# pyra_dvt1_power-2_0.net
KiCad netlist of a schematic drawn in Altium Designer
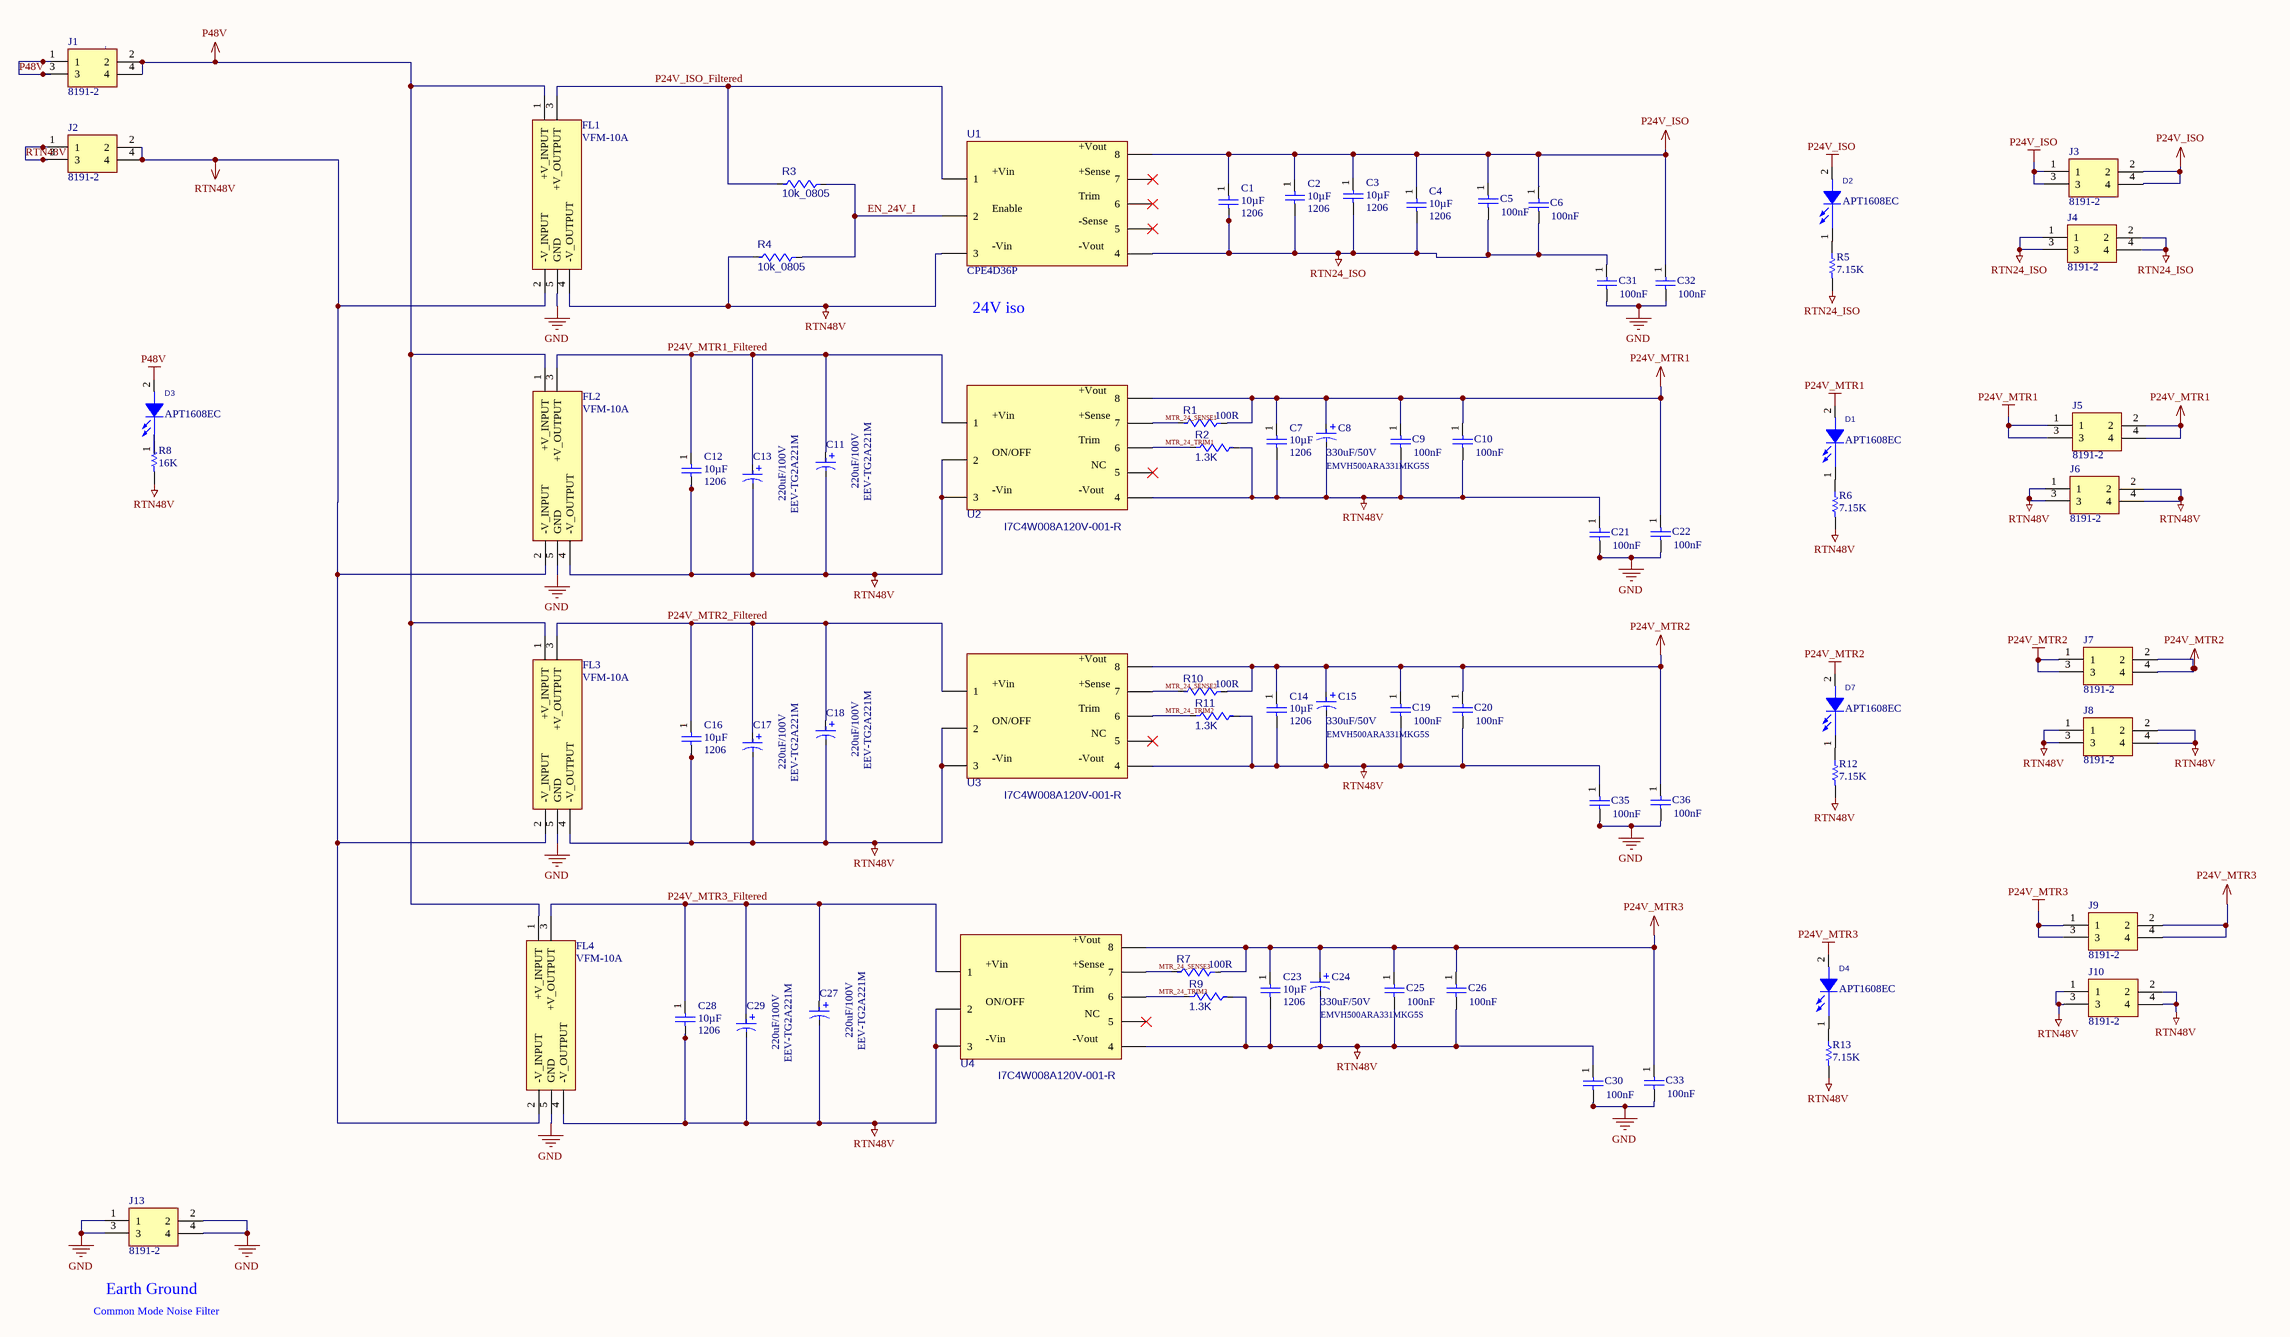
[diagram p0: pyra_dvt1_power-2.0.SchDoc]

(export (version "E")
  (design (tool "Eeschema 10.0.6"))
  (components
    (comp (ref "C1")
      (value "10µF")
      (footprint "1206")
      (description "CAP CER 10UF 50V X5R 1206")
      (fields
        (field (name "MANUFACTURER") "TDK Corporation")
        (field (name "TOLERANCE") "±20%")
        (field (name "SIZE") "1206")
      )
      (libsource (lib "bct") (part "C1206_10UF_50V"))
    )
    (comp (ref "C2")
      (value "10µF")
      (footprint "1206")
      (description "CAP CER 10UF 50V X5R 1206")
      (fields
        (field (name "MANUFACTURER") "TDK Corporation")
        (field (name "TOLERANCE") "±20%")
        (field (name "SIZE") "1206")
      )
      (libsource (lib "bct") (part "C1206_10UF_50V"))
    )
    (comp (ref "C3")
      (value "10µF")
      (footprint "1206")
      (description "CAP CER 10UF 50V X5R 1206")
      (fields
        (field (name "MANUFACTURER") "TDK Corporation")
        (field (name "TOLERANCE") "±20%")
        (field (name "SIZE") "1206")
      )
      (libsource (lib "bct") (part "C1206_10UF_50V"))
    )
    (comp (ref "C4")
      (value "10µF")
      (footprint "1206")
      (description "CAP CER 10UF 50V X5R 1206")
      (fields
        (field (name "MANUFACTURER") "TDK Corporation")
        (field (name "TOLERANCE") "±20%")
        (field (name "SIZE") "1206")
      )
      (libsource (lib "bct") (part "C1206_10UF_50V"))
    )
    (comp (ref "C5")
      (value "100nF")
      (footprint "0603R(1608)")
      (description "CAP CER 0.1UF 50V X5R 0603")
      (fields (field (name "MANUFACTURER") "TDK Corporation") (field (name "TOLERANCE") "±10%"))
      (libsource (lib "bct") (part "C0603_100NF_50V"))
    )
    (comp (ref "C6")
      (value "100nF")
      (footprint "0603R(1608)")
      (description "CAP CER 0.1UF 50V X5R 0603")
      (fields (field (name "MANUFACTURER") "TDK Corporation") (field (name "TOLERANCE") "±10%"))
      (libsource (lib "bct") (part "C0603_100NF_50V"))
    )
    (comp (ref "C7")
      (value "10µF")
      (footprint "1206")
      (description "CAP CER 10UF 50V X5R 1206")
      (fields
        (field (name "MANUFACTURER") "TDK Corporation")
        (field (name "TOLERANCE") "±20%")
        (field (name "SIZE") "1206")
      )
      (libsource (lib "bct") (part "C1206_10UF_50V"))
    )
    (comp (ref "C8")
      (value "330uF/50V")
      (footprint "EMVH500ARA331MKG5S")
      (description "CAP ALUM 330UF 20% 50V SMD")
      (fields
        (field (name "MANUFACTURER") "United Chemi-con")
        (field (name "MANUFACTURER PART NUMBER") "EMVH500ARA331MKG5S")
        (field (name "TOLERANCE") "20%")
        (field (name "_VERIFIED FOOTPRINT") ".mfr-pn? footprint?")
        (field (name "_VERIFIED SYMBOL") ".mfr-pn?")
        (field (name "_VERIFIED BOM") ".mfr-pn?")
      )
      (libsource (lib "PowerPCB") (part "CAP POLAR  330uF"))
    )
    (comp (ref "C9")
      (value "100nF")
      (footprint "0603R(1608)")
      (description "CAP CER 0.1UF 50V X5R 0603")
      (fields (field (name "MANUFACTURER") "TDK Corporation") (field (name "TOLERANCE") "±10%"))
      (libsource (lib "bct") (part "C0603_100NF_50V"))
    )
    (comp (ref "C10")
      (value "100nF")
      (footprint "0603R(1608)")
      (description "CAP CER 0.1UF 50V X5R 0603")
      (fields (field (name "MANUFACTURER") "TDK Corporation") (field (name "TOLERANCE") "±10%"))
      (libsource (lib "bct") (part "C0603_100NF_50V"))
    )
    (comp (ref "C11")
      (value "220uF/100V")
      (footprint "EMVH101GDA221MMN0S")
      (description "CAP ALUM 220UF 20% 100V SMD")
      (fields
        (field (name "MANUFACTURER") "Panasonic")
        (field (name "MANUFACTURER PART NUMBER") "EEV-TG2A221M")
        (field (name "TOLERANCE") "20%")
        (field (name "_VERIFIED FOOTPRINT") ".mfr-pn? footprint?")
        (field (name "_VERIFIED SYMBOL") ".mfr-pn?")
        (field (name "_VERIFIED BOM") ".mfr-pn?")
      )
      (libsource (lib "PowerPCB") (part "CAP POLAR  220uF"))
    )
    (comp (ref "C12")
      (value "10µF")
      (footprint "1206")
      (description "CAP CER 10UF 50V X5R 1206")
      (fields
        (field (name "MANUFACTURER") "TDK Corporation")
        (field (name "TOLERANCE") "±20%")
        (field (name "SIZE") "1206")
      )
      (libsource (lib "bct") (part "C1206_10UF_50V"))
    )
    (comp (ref "C13")
      (value "220uF/100V")
      (footprint "EMVH101GDA221MMN0S")
      (description "CAP ALUM 220UF 20% 100V SMD")
      (fields
        (field (name "MANUFACTURER") "Panasonic")
        (field (name "MANUFACTURER PART NUMBER") "EEV-TG2A221M")
        (field (name "TOLERANCE") "20%")
        (field (name "_VERIFIED FOOTPRINT") ".mfr-pn? footprint?")
        (field (name "_VERIFIED SYMBOL") ".mfr-pn?")
        (field (name "_VERIFIED BOM") ".mfr-pn?")
      )
      (libsource (lib "PowerPCB") (part "CAP POLAR  220uF"))
    )
    (comp (ref "C14")
      (value "10µF")
      (footprint "1206")
      (description "CAP CER 10UF 50V X5R 1206")
      (fields
        (field (name "MANUFACTURER") "TDK Corporation")
        (field (name "TOLERANCE") "±20%")
        (field (name "SIZE") "1206")
      )
      (libsource (lib "bct") (part "C1206_10UF_50V"))
    )
    (comp (ref "C15")
      (value "330uF/50V")
      (footprint "EMVH500ARA331MKG5S")
      (description "CAP ALUM 330UF 20% 50V SMD")
      (fields
        (field (name "MANUFACTURER") "United Chemi-con")
        (field (name "MANUFACTURER PART NUMBER") "EMVH500ARA331MKG5S")
        (field (name "TOLERANCE") "20%")
        (field (name "_VERIFIED FOOTPRINT") ".mfr-pn? footprint?")
        (field (name "_VERIFIED SYMBOL") ".mfr-pn?")
        (field (name "_VERIFIED BOM") ".mfr-pn?")
      )
      (libsource (lib "PowerPCB") (part "CAP POLAR  330uF"))
    )
    (comp (ref "C16")
      (value "10µF")
      (footprint "1206")
      (description "CAP CER 10UF 50V X5R 1206")
      (fields
        (field (name "MANUFACTURER") "TDK Corporation")
        (field (name "TOLERANCE") "±20%")
        (field (name "SIZE") "1206")
      )
      (libsource (lib "bct") (part "C1206_10UF_50V"))
    )
    (comp (ref "C17")
      (value "220uF/100V")
      (footprint "EMVH101GDA221MMN0S")
      (description "CAP ALUM 220UF 20% 100V SMD")
      (fields
        (field (name "MANUFACTURER") "Panasonic")
        (field (name "MANUFACTURER PART NUMBER") "EEV-TG2A221M")
        (field (name "TOLERANCE") "20%")
        (field (name "_VERIFIED FOOTPRINT") ".mfr-pn? footprint?")
        (field (name "_VERIFIED SYMBOL") ".mfr-pn?")
        (field (name "_VERIFIED BOM") ".mfr-pn?")
      )
      (libsource (lib "PowerPCB") (part "CAP POLAR  220uF"))
    )
    (comp (ref "C18")
      (value "220uF/100V")
      (footprint "EMVH101GDA221MMN0S")
      (description "CAP ALUM 220UF 20% 100V SMD")
      (fields
        (field (name "MANUFACTURER") "Panasonic")
        (field (name "MANUFACTURER PART NUMBER") "EEV-TG2A221M")
        (field (name "TOLERANCE") "20%")
        (field (name "_VERIFIED FOOTPRINT") ".mfr-pn? footprint?")
        (field (name "_VERIFIED SYMBOL") ".mfr-pn?")
        (field (name "_VERIFIED BOM") ".mfr-pn?")
      )
      (libsource (lib "PowerPCB") (part "CAP POLAR  220uF"))
    )
    (comp (ref "C19")
      (value "100nF")
      (footprint "0603R(1608)")
      (description "CAP CER 0.1UF 50V X5R 0603")
      (fields (field (name "MANUFACTURER") "TDK Corporation") (field (name "TOLERANCE") "±10%"))
      (libsource (lib "bct") (part "C0603_100NF_50V"))
    )
    (comp (ref "C20")
      (value "100nF")
      (footprint "0603R(1608)")
      (description "CAP CER 0.1UF 50V X5R 0603")
      (fields (field (name "MANUFACTURER") "TDK Corporation") (field (name "TOLERANCE") "±10%"))
      (libsource (lib "bct") (part "C0603_100NF_50V"))
    )
    (comp (ref "C21")
      (value "100nF")
      (footprint "0603R(1608)")
      (description "CAP CER 0.1UF 50V X5R 0603")
      (fields (field (name "MANUFACTURER") "TDK Corporation") (field (name "TOLERANCE") "±10%"))
      (libsource (lib "bct") (part "C0603_100NF_50V"))
    )
    (comp (ref "C22")
      (value "100nF")
      (footprint "0603R(1608)")
      (description "CAP CER 0.1UF 50V X5R 0603")
      (fields (field (name "MANUFACTURER") "TDK Corporation") (field (name "TOLERANCE") "±10%"))
      (libsource (lib "bct") (part "C0603_100NF_50V"))
    )
    (comp (ref "C23")
      (value "10µF")
      (footprint "1206")
      (description "CAP CER 10UF 50V X5R 1206")
      (fields
        (field (name "MANUFACTURER") "TDK Corporation")
        (field (name "TOLERANCE") "±20%")
        (field (name "SIZE") "1206")
      )
      (libsource (lib "bct") (part "C1206_10UF_50V"))
    )
    (comp (ref "C24")
      (value "330uF/50V")
      (footprint "EMVH500ARA331MKG5S")
      (description "CAP ALUM 330UF 20% 50V SMD")
      (fields
        (field (name "MANUFACTURER") "United Chemi-con")
        (field (name "MANUFACTURER PART NUMBER") "EMVH500ARA331MKG5S")
        (field (name "TOLERANCE") "20%")
        (field (name "_VERIFIED FOOTPRINT") ".mfr-pn? footprint?")
        (field (name "_VERIFIED SYMBOL") ".mfr-pn?")
        (field (name "_VERIFIED BOM") ".mfr-pn?")
      )
      (libsource (lib "PowerPCB") (part "CAP POLAR  330uF"))
    )
    (comp (ref "C25")
      (value "100nF")
      (footprint "0603R(1608)")
      (description "CAP CER 0.1UF 50V X5R 0603")
      (fields (field (name "MANUFACTURER") "TDK Corporation") (field (name "TOLERANCE") "±10%"))
      (libsource (lib "bct") (part "C0603_100NF_50V"))
    )
    (comp (ref "C26")
      (value "100nF")
      (footprint "0603R(1608)")
      (description "CAP CER 0.1UF 50V X5R 0603")
      (fields (field (name "MANUFACTURER") "TDK Corporation") (field (name "TOLERANCE") "±10%"))
      (libsource (lib "bct") (part "C0603_100NF_50V"))
    )
    (comp (ref "C27")
      (value "220uF/100V")
      (footprint "EMVH101GDA221MMN0S")
      (description "CAP ALUM 220UF 20% 100V SMD")
      (fields
        (field (name "MANUFACTURER") "Panasonic")
        (field (name "MANUFACTURER PART NUMBER") "EEV-TG2A221M")
        (field (name "TOLERANCE") "20%")
        (field (name "_VERIFIED FOOTPRINT") ".mfr-pn? footprint?")
        (field (name "_VERIFIED SYMBOL") ".mfr-pn?")
        (field (name "_VERIFIED BOM") ".mfr-pn?")
      )
      (libsource (lib "PowerPCB") (part "CAP POLAR  220uF"))
    )
    (comp (ref "C28")
      (value "10µF")
      (footprint "1206")
      (description "CAP CER 10UF 50V X5R 1206")
      (fields
        (field (name "MANUFACTURER") "TDK Corporation")
        (field (name "TOLERANCE") "±20%")
        (field (name "SIZE") "1206")
      )
      (libsource (lib "bct") (part "C1206_10UF_50V"))
    )
    (comp (ref "C29")
      (value "220uF/100V")
      (footprint "EMVH101GDA221MMN0S")
      (description "CAP ALUM 220UF 20% 100V SMD")
      (fields
        (field (name "MANUFACTURER") "Panasonic")
        (field (name "MANUFACTURER PART NUMBER") "EEV-TG2A221M")
        (field (name "TOLERANCE") "20%")
        (field (name "_VERIFIED FOOTPRINT") ".mfr-pn? footprint?")
        (field (name "_VERIFIED SYMBOL") ".mfr-pn?")
        (field (name "_VERIFIED BOM") ".mfr-pn?")
      )
      (libsource (lib "PowerPCB") (part "CAP POLAR  220uF"))
    )
    (comp (ref "C30")
      (value "100nF")
      (footprint "0603R(1608)")
      (description "CAP CER 0.1UF 50V X5R 0603")
      (fields (field (name "MANUFACTURER") "TDK Corporation") (field (name "TOLERANCE") "±10%"))
      (libsource (lib "bct") (part "C0603_100NF_50V"))
    )
    (comp (ref "C31")
      (value "100nF")
      (footprint "0603R(1608)")
      (description "CAP CER 0.1UF 50V X5R 0603")
      (fields (field (name "MANUFACTURER") "TDK Corporation") (field (name "TOLERANCE") "±10%"))
      (libsource (lib "bct") (part "C0603_100NF_50V"))
    )
    (comp (ref "C32")
      (value "100nF")
      (footprint "0603R(1608)")
      (description "CAP CER 0.1UF 50V X5R 0603")
      (fields (field (name "MANUFACTURER") "TDK Corporation") (field (name "TOLERANCE") "±10%"))
      (libsource (lib "bct") (part "C0603_100NF_50V"))
    )
    (comp (ref "C33")
      (value "100nF")
      (footprint "0603R(1608)")
      (description "CAP CER 0.1UF 50V X5R 0603")
      (fields (field (name "MANUFACTURER") "TDK Corporation") (field (name "TOLERANCE") "±10%"))
      (libsource (lib "bct") (part "C0603_100NF_50V"))
    )
    (comp (ref "C35")
      (value "100nF")
      (footprint "0603R(1608)")
      (description "CAP CER 0.1UF 50V X5R 0603")
      (fields (field (name "MANUFACTURER") "TDK Corporation") (field (name "TOLERANCE") "±10%"))
      (libsource (lib "bct") (part "C0603_100NF_50V"))
    )
    (comp (ref "C36")
      (value "100nF")
      (footprint "0603R(1608)")
      (description "CAP CER 0.1UF 50V X5R 0603")
      (fields (field (name "MANUFACTURER") "TDK Corporation") (field (name "TOLERANCE") "±10%"))
      (libsource (lib "bct") (part "C0603_100NF_50V"))
    )
    (comp (ref "D1")
      (value "APT1608EC")
      (footprint "APT1608EC")
      (description "red, 0603")
      (fields
        (field (name "MANUFACTURER") "Kingbright")
        (field (name "MANUFACTURER PART NUMBER") "APT1608EC")
      )
      (libsource (lib "bct") (part "LED_red_0603"))
    )
    (comp (ref "D2")
      (value "APT1608EC")
      (footprint "APT1608EC")
      (description "red, 0603")
      (fields
        (field (name "MANUFACTURER") "Kingbright")
        (field (name "MANUFACTURER PART NUMBER") "APT1608EC")
      )
      (libsource (lib "bct") (part "LED_red_0603"))
    )
    (comp (ref "D3")
      (value "APT1608EC")
      (footprint "APT1608EC")
      (description "red, 0603")
      (fields
        (field (name "MANUFACTURER") "Kingbright")
        (field (name "MANUFACTURER PART NUMBER") "APT1608EC")
      )
      (libsource (lib "bct") (part "LED_red_0603"))
    )
    (comp (ref "D4")
      (value "APT1608EC")
      (footprint "APT1608EC")
      (description "red, 0603")
      (fields
        (field (name "MANUFACTURER") "Kingbright")
        (field (name "MANUFACTURER PART NUMBER") "APT1608EC")
      )
      (libsource (lib "bct") (part "LED_red_0603"))
    )
    (comp (ref "D7")
      (value "APT1608EC")
      (footprint "APT1608EC")
      (description "red, 0603")
      (fields
        (field (name "MANUFACTURER") "Kingbright")
        (field (name "MANUFACTURER PART NUMBER") "APT1608EC")
      )
      (libsource (lib "bct") (part "LED_red_0603"))
    )
    (comp (ref "FL1")
      (value "VFM-10A")
      (footprint "VFM10A")
      (description "Power Line Filters 0-75Vin 10A DC EMI Filter")
      (fields (field (name "MOUSER PART NUMBER") "490-VFM-10A"))
      (libsource (lib "Bellwether Coffee") (part "VFM-10A"))
    )
    (comp (ref "FL2")
      (value "VFM-10A")
      (footprint "VFM10A")
      (description "Power Line Filters 0-75Vin 10A DC EMI Filter")
      (fields (field (name "MOUSER PART NUMBER") "490-VFM-10A"))
      (libsource (lib "Bellwether Coffee") (part "VFM-10A"))
    )
    (comp (ref "FL3")
      (value "VFM-10A")
      (footprint "VFM10A")
      (description "Power Line Filters 0-75Vin 10A DC EMI Filter")
      (fields (field (name "MOUSER PART NUMBER") "490-VFM-10A"))
      (libsource (lib "Bellwether Coffee") (part "VFM-10A"))
    )
    (comp (ref "FL4")
      (value "VFM-10A")
      (footprint "VFM10A")
      (description "Power Line Filters 0-75Vin 10A DC EMI Filter")
      (fields (field (name "MOUSER PART NUMBER") "490-VFM-10A"))
      (libsource (lib "Bellwether Coffee") (part "VFM-10A"))
    )
    (comp (ref "J1")
      (value "8191-2")
      (footprint "81912")
      (description "Keystone, Brass Screw Terminal, 22  14 AWG, 15A")
      (fields (field (name "MOUSER PART NUMBER") "534-8191-2"))
      (libsource (lib "Bellwether Coffee") (part "8191-2"))
    )
    (comp (ref "J2")
      (value "8191-2")
      (footprint "81912")
      (description "Keystone, Brass Screw Terminal, 22  14 AWG, 15A")
      (fields (field (name "MOUSER PART NUMBER") "534-8191-2"))
      (libsource (lib "Bellwether Coffee") (part "8191-2"))
    )
    (comp (ref "J3")
      (value "8191-2")
      (footprint "81912")
      (description "Keystone, Brass Screw Terminal, 22  14 AWG, 15A")
      (fields (field (name "MOUSER PART NUMBER") "534-8191-2"))
      (libsource (lib "Bellwether Coffee") (part "8191-2"))
    )
    (comp (ref "J4")
      (value "8191-2")
      (footprint "81912")
      (description "Keystone, Brass Screw Terminal, 22  14 AWG, 15A")
      (fields (field (name "MOUSER PART NUMBER") "534-8191-2"))
      (libsource (lib "Bellwether Coffee") (part "8191-2"))
    )
    (comp (ref "J5")
      (value "8191-2")
      (footprint "81912")
      (description "Keystone, Brass Screw Terminal, 22  14 AWG, 15A")
      (fields (field (name "MOUSER PART NUMBER") "534-8191-2"))
      (libsource (lib "Bellwether Coffee") (part "8191-2"))
    )
    (comp (ref "J6")
      (value "8191-2")
      (footprint "81912")
      (description "Keystone, Brass Screw Terminal, 22  14 AWG, 15A")
      (fields (field (name "MOUSER PART NUMBER") "534-8191-2"))
      (libsource (lib "Bellwether Coffee") (part "8191-2"))
    )
    (comp (ref "J7")
      (value "8191-2")
      (footprint "81912")
      (description "Keystone, Brass Screw Terminal, 22  14 AWG, 15A")
      (fields (field (name "MOUSER PART NUMBER") "534-8191-2"))
      (libsource (lib "Bellwether Coffee") (part "8191-2"))
    )
    (comp (ref "J8")
      (value "8191-2")
      (footprint "81912")
      (description "Keystone, Brass Screw Terminal, 22  14 AWG, 15A")
      (fields (field (name "MOUSER PART NUMBER") "534-8191-2"))
      (libsource (lib "Bellwether Coffee") (part "8191-2"))
    )
    (comp (ref "J9")
      (value "8191-2")
      (footprint "81912")
      (description "Keystone, Brass Screw Terminal, 22  14 AWG, 15A")
      (fields (field (name "MOUSER PART NUMBER") "534-8191-2"))
      (libsource (lib "Bellwether Coffee") (part "8191-2"))
    )
    (comp (ref "J10")
      (value "8191-2")
      (footprint "81912")
      (description "Keystone, Brass Screw Terminal, 22  14 AWG, 15A")
      (fields (field (name "MOUSER PART NUMBER") "534-8191-2"))
      (libsource (lib "Bellwether Coffee") (part "8191-2"))
    )
    (comp (ref "J13")
      (value "8191-2")
      (footprint "81912")
      (description "Keystone, Brass Screw Terminal, 22  14 AWG, 15A")
      (fields (field (name "MOUSER PART NUMBER") "534-8191-2"))
      (libsource (lib "Bellwether Coffee") (part "8191-2"))
    )
    (comp (ref "R1")
      (value "?")
      (footprint "0805")
      (description "RES 100 OHM 5% 1/4W 0805")
      (fields
        (field (name "MANUFACTURER") "KOA")
        (field (name "MANUFACTURER PART NUMBER") "RK73B2ATTD101J")
        (field (name "RESISTANCE") "100R")
        (field (name "_VERIFIED FOOTPRINT") ".mfr-pn? footprint?")
        (field (name "_VERIFIED BOM") ".mfr-pn?")
        (field (name "_VERIFIED SYMBOL") ".mfr-pn?")
      )
      (libsource (lib "Generics-MT") (part "RES .val? 0805"))
    )
    (comp (ref "R2")
      (value "1.3K")
      (footprint "0603R(1608)")
      (description "RES SMD 1.3K OHM 1% 1/10W 0603")
      (fields
        (field (name "MANUFACTURER") "Panasonic")
        (field (name "MANUFACTURER PART NUMBER") "ERJ-3EKF1301V")
        (field (name "_VERIFIED FOOTPRINT") ".mfr-pn? footprint?")
        (field (name "_VERIFIED SYMBOL") ".mfr-pn?")
        (field (name "_VERIFIED BOM") ".mfr-pn?")
      )
      (libsource (lib "Generics-MT") (part "RES .val? .pkg?"))
    )
    (comp (ref "R3")
      (value "10k_0805")
      (footprint "0805")
      (description "Res Thick Film 0805 10K Ohm 1% 0.125W ±100ppm/°C Molded SMD Paper T/R")
      (fields
        (field (name "MANUFACTURER") "Stackpole Electronics")
        (field (name "MANUFACTURER PART NUMBER") "RMCF0805FT10K0")
      )
      (libsource (lib "PowerPCB") (part "RES 10k_0805"))
    )
    (comp (ref "R4")
      (value "10k_0805")
      (footprint "0805")
      (description "Res Thick Film 0805 10K Ohm 1% 0.125W ±100ppm/°C Molded SMD Paper T/R")
      (fields
        (field (name "MANUFACTURER") "Stackpole Electronics")
        (field (name "MANUFACTURER PART NUMBER") "RMCF0805FT10K0")
      )
      (libsource (lib "PowerPCB") (part "RES 10k_0805"))
    )
    (comp (ref "R5")
      (value "10k")
      (footprint "0603R(1608)")
      (description "RES SMD 10K OHM 5% 1/10W 0603")
      (fields
        (field (name "TOLERANCE") "±1%")
        (field (name "MANUFACTURER") "Panasonic Electronic Components")
        (field (name "RESISTANCE (OHMS)") "7.15K")
      )
      (libsource (lib "Control_1") (part "RES-0603-10K_1"))
    )
    (comp (ref "R6")
      (value "10k")
      (footprint "0603R(1608)")
      (description "RES SMD 10K OHM 5% 1/10W 0603")
      (fields
        (field (name "TOLERANCE") "±1%")
        (field (name "MANUFACTURER") "Panasonic Electronic Components")
        (field (name "RESISTANCE (OHMS)") "7.15K")
      )
      (libsource (lib "Control_1") (part "RES-0603-10K_1"))
    )
    (comp (ref "R7")
      (value "?")
      (footprint "0805")
      (description "RES 100 OHM 5% 1/4W 0805")
      (fields
        (field (name "MANUFACTURER") "KOA")
        (field (name "MANUFACTURER PART NUMBER") "RK73B2ATTD101J")
        (field (name "RESISTANCE") "100R")
        (field (name "_VERIFIED FOOTPRINT") ".mfr-pn? footprint?")
        (field (name "_VERIFIED BOM") ".mfr-pn?")
        (field (name "_VERIFIED SYMBOL") ".mfr-pn?")
      )
      (libsource (lib "Generics-MT") (part "RES .val? 0805"))
    )
    (comp (ref "R8")
      (value "10k")
      (footprint "0603R(1608)")
      (description "RES SMD 10K OHM 5% 1/10W 0603")
      (fields
        (field (name "TOLERANCE") "±1%")
        (field (name "MANUFACTURER") "Panasonic Electronic Components")
        (field (name "RESISTANCE (OHMS)") "16K")
      )
      (libsource (lib "Control_1") (part "RES-0603-10K_1"))
    )
    (comp (ref "R9")
      (value "1.3K")
      (footprint "0603R(1608)")
      (description "RES SMD 1.3K OHM 1% 1/10W 0603")
      (fields
        (field (name "MANUFACTURER") "Panasonic")
        (field (name "MANUFACTURER PART NUMBER") "ERJ-3EKF1301V")
        (field (name "_VERIFIED FOOTPRINT") ".mfr-pn? footprint?")
        (field (name "_VERIFIED SYMBOL") ".mfr-pn?")
        (field (name "_VERIFIED BOM") ".mfr-pn?")
      )
      (libsource (lib "Generics-MT") (part "RES .val? .pkg?"))
    )
    (comp (ref "R10")
      (value "?")
      (footprint "0805")
      (description "RES 100 OHM 5% 1/4W 0805")
      (fields
        (field (name "MANUFACTURER") "KOA")
        (field (name "MANUFACTURER PART NUMBER") "RK73B2ATTD101J")
        (field (name "RESISTANCE") "100R")
        (field (name "_VERIFIED FOOTPRINT") ".mfr-pn? footprint?")
        (field (name "_VERIFIED BOM") ".mfr-pn?")
        (field (name "_VERIFIED SYMBOL") ".mfr-pn?")
      )
      (libsource (lib "Generics-MT") (part "RES .val? 0805"))
    )
    (comp (ref "R11")
      (value "1.3K")
      (footprint "0603R(1608)")
      (description "RES SMD 1.3K OHM 1% 1/10W 0603")
      (fields
        (field (name "MANUFACTURER") "Panasonic")
        (field (name "MANUFACTURER PART NUMBER") "ERJ-3EKF1301V")
        (field (name "_VERIFIED FOOTPRINT") ".mfr-pn? footprint?")
        (field (name "_VERIFIED SYMBOL") ".mfr-pn?")
        (field (name "_VERIFIED BOM") ".mfr-pn?")
      )
      (libsource (lib "Generics-MT") (part "RES .val? .pkg?"))
    )
    (comp (ref "R12")
      (value "10k")
      (footprint "0603R(1608)")
      (description "RES SMD 10K OHM 5% 1/10W 0603")
      (fields
        (field (name "TOLERANCE") "±1%")
        (field (name "MANUFACTURER") "Panasonic Electronic Components")
        (field (name "RESISTANCE (OHMS)") "7.15K")
      )
      (libsource (lib "Control_1") (part "RES-0603-10K_1"))
    )
    (comp (ref "R13")
      (value "10k")
      (footprint "0603R(1608)")
      (description "RES SMD 10K OHM 5% 1/10W 0603")
      (fields
        (field (name "TOLERANCE") "±1%")
        (field (name "MANUFACTURER") "Panasonic Electronic Components")
        (field (name "RESISTANCE (OHMS)") "7.15K")
      )
      (libsource (lib "Control_1") (part "RES-0603-10K_1"))
    )
    (comp (ref "U1")
      (value "CPE4D36P")
      (footprint "CPE4D36N")
      (description "Isolated Module DC DC Converter 1 Output 24V    4A 18V - 72V Input")
      (fields
        (field (name "MANUFACTURER") "Semiconductor Circuits, Inc.")
        (field (name "MANUFACTURER PART NUMBER") "CPE4D36P")
        (field (name "MANUFACTURER2 PART NUMBER") "ERS3240N004N25W")
      )
      (libsource (lib "PowerPCB") (part "CPE4D36N"))
    )
    (comp (ref "U2")
      (value "I7C4W008A120V-001-R")
      (footprint "CPT2D36P")
      (description "DC DC CONVERTER 9.6-48V OUTPUT 300W 8A 9V - 53V INPUT")
      (fields (field (name "MANUFACTURER") "TDK-Lambda"))
      (libsource (lib "PowerPCB") (part "I7C4W008A120V-001-R"))
    )
    (comp (ref "U3")
      (value "I7C4W008A120V-001-R")
      (footprint "CPT2D36P")
      (description "DC DC CONVERTER 9.6-48V OUTPUT 300W 8A 9V - 53V INPUT")
      (fields (field (name "MANUFACTURER") "TDK-Lambda"))
      (libsource (lib "PowerPCB") (part "I7C4W008A120V-001-R"))
    )
    (comp (ref "U4")
      (value "I7C4W008A120V-001-R")
      (footprint "CPT2D36P")
      (description "DC DC CONVERTER 9.6-48V OUTPUT 300W 8A 9V - 53V INPUT")
      (fields (field (name "MANUFACTURER") "TDK-Lambda"))
      (libsource (lib "PowerPCB") (part "I7C4W008A120V-001-R"))
    )
  )
  (nets
    (net (code "1") (name "/EN_24V_I") (class "Default")
      (node (ref "R3") (pin "2") (pinfunction "2_2") (pintype "passive"))
      (node (ref "R4") (pin "2") (pinfunction "2_2") (pintype "passive"))
      (node (ref "U1") (pin "2") (pinfunction "2_2") (pintype "passive"))
    )
    (net (code "2") (name "/MTR_24_SENSE1") (class "Default")
      (node (ref "R1") (pin "1") (pinfunction "1_1") (pintype "passive"))
      (node (ref "U2") (pin "7") (pinfunction "7_7") (pintype "passive"))
    )
    (net (code "3") (name "/MTR_24_SENSE2") (class "Default")
      (node (ref "R10") (pin "1") (pinfunction "1_1") (pintype "passive"))
      (node (ref "U3") (pin "7") (pinfunction "7_7") (pintype "passive"))
    )
    (net (code "4") (name "/MTR_24_SENSE3") (class "Default")
      (node (ref "R7") (pin "1") (pinfunction "1_1") (pintype "passive"))
      (node (ref "U4") (pin "7") (pinfunction "7_7") (pintype "passive"))
    )
    (net (code "5") (name "/MTR_24_TRIM1") (class "Default")
      (node (ref "R2") (pin "2") (pinfunction "2_2") (pintype "passive"))
      (node (ref "U2") (pin "6") (pinfunction "6_6") (pintype "passive"))
    )
    (net (code "6") (name "/MTR_24_TRIM2") (class "Default")
      (node (ref "R11") (pin "2") (pinfunction "2_2") (pintype "passive"))
      (node (ref "U3") (pin "6") (pinfunction "6_6") (pintype "passive"))
    )
    (net (code "7") (name "/MTR_24_TRIM3") (class "Default")
      (node (ref "R9") (pin "2") (pinfunction "2_2") (pintype "passive"))
      (node (ref "U4") (pin "6") (pinfunction "6_6") (pintype "passive"))
    )
    (net (code "8") (name "/P24V_ISO_Filtered") (class "Default")
      (node (ref "FL1") (pin "3") (pinfunction "+V_OUTPUT_3") (pintype "passive"))
      (node (ref "R3") (pin "1") (pinfunction "1_1") (pintype "passive"))
      (node (ref "U1") (pin "1") (pinfunction "1_1") (pintype "passive"))
    )
    (net (code "9") (name "/P24V_MTR1_Filtered") (class "Default")
      (node (ref "C11") (pin "1") (pinfunction "1_1") (pintype "passive"))
      (node (ref "C12") (pin "1") (pinfunction "1_1") (pintype "passive"))
      (node (ref "C13") (pin "1") (pinfunction "1_1") (pintype "passive"))
      (node (ref "FL2") (pin "3") (pinfunction "+V_OUTPUT_3") (pintype "passive"))
      (node (ref "U2") (pin "1") (pinfunction "1_1") (pintype "passive"))
    )
    (net (code "10") (name "/P24V_MTR2_Filtered") (class "Default")
      (node (ref "C16") (pin "1") (pinfunction "1_1") (pintype "passive"))
      (node (ref "C17") (pin "1") (pinfunction "1_1") (pintype "passive"))
      (node (ref "C18") (pin "1") (pinfunction "1_1") (pintype "passive"))
      (node (ref "FL3") (pin "3") (pinfunction "+V_OUTPUT_3") (pintype "passive"))
      (node (ref "U3") (pin "1") (pinfunction "1_1") (pintype "passive"))
    )
    (net (code "11") (name "/P24V_MTR3_Filtered") (class "Default")
      (node (ref "C27") (pin "1") (pinfunction "1_1") (pintype "passive"))
      (node (ref "C28") (pin "1") (pinfunction "1_1") (pintype "passive"))
      (node (ref "C29") (pin "1") (pinfunction "1_1") (pintype "passive"))
      (node (ref "FL4") (pin "3") (pinfunction "+V_OUTPUT_3") (pintype "passive"))
      (node (ref "U4") (pin "1") (pinfunction "1_1") (pintype "passive"))
    )
    (net (code "12") (name "GND") (class "Default")
      (node (ref "C21") (pin "2") (pinfunction "2_2") (pintype "passive"))
      (node (ref "C22") (pin "2") (pinfunction "2_2") (pintype "passive"))
      (node (ref "C30") (pin "2") (pinfunction "2_2") (pintype "passive"))
      (node (ref "C31") (pin "2") (pinfunction "2_2") (pintype "passive"))
      (node (ref "C32") (pin "2") (pinfunction "2_2") (pintype "passive"))
      (node (ref "C33") (pin "2") (pinfunction "2_2") (pintype "passive"))
      (node (ref "C35") (pin "2") (pinfunction "2_2") (pintype "passive"))
      (node (ref "C36") (pin "2") (pinfunction "2_2") (pintype "passive"))
      (node (ref "FL1") (pin "5") (pinfunction "GND_5") (pintype "passive"))
      (node (ref "FL2") (pin "5") (pinfunction "GND_5") (pintype "passive"))
      (node (ref "FL3") (pin "5") (pinfunction "GND_5") (pintype "passive"))
      (node (ref "FL4") (pin "5") (pinfunction "GND_5") (pintype "passive"))
      (node (ref "J13") (pin "1") (pinfunction "1_1") (pintype "passive"))
      (node (ref "J13") (pin "2") (pinfunction "2_2") (pintype "passive"))
      (node (ref "J13") (pin "3") (pinfunction "3_3") (pintype "passive"))
      (node (ref "J13") (pin "4") (pinfunction "4_4") (pintype "passive"))
    )
    (net (code "13") (name "Net-(D1-CATHODE)") (class "Default")
      (node (ref "D1") (pin "1") (pinfunction "CATHODE_1") (pintype "passive"))
      (node (ref "R6") (pin "1") (pinfunction "1_1") (pintype "passive"))
    )
    (net (code "14") (name "Net-(D2-CATHODE)") (class "Default")
      (node (ref "D2") (pin "1") (pinfunction "CATHODE_1") (pintype "passive"))
      (node (ref "R5") (pin "1") (pinfunction "1_1") (pintype "passive"))
    )
    (net (code "15") (name "Net-(D3-CATHODE)") (class "Default")
      (node (ref "D3") (pin "1") (pinfunction "CATHODE_1") (pintype "passive"))
      (node (ref "R8") (pin "1") (pinfunction "1_1") (pintype "passive"))
    )
    (net (code "16") (name "Net-(D4-CATHODE)") (class "Default")
      (node (ref "D4") (pin "1") (pinfunction "CATHODE_1") (pintype "passive"))
      (node (ref "R13") (pin "1") (pinfunction "1_1") (pintype "passive"))
    )
    (net (code "17") (name "Net-(D7-CATHODE)") (class "Default")
      (node (ref "D7") (pin "1") (pinfunction "CATHODE_1") (pintype "passive"))
      (node (ref "R12") (pin "1") (pinfunction "1_1") (pintype "passive"))
    )
    (net (code "18") (name "P24V_ISO") (class "Default")
      (node (ref "C1") (pin "1") (pinfunction "1_1") (pintype "passive"))
      (node (ref "C2") (pin "1") (pinfunction "1_1") (pintype "passive"))
      (node (ref "C3") (pin "1") (pinfunction "1_1") (pintype "passive"))
      (node (ref "C32") (pin "1") (pinfunction "1_1") (pintype "passive"))
      (node (ref "C4") (pin "1") (pinfunction "1_1") (pintype "passive"))
      (node (ref "C5") (pin "1") (pinfunction "1_1") (pintype "passive"))
      (node (ref "C6") (pin "1") (pinfunction "1_1") (pintype "passive"))
      (node (ref "D2") (pin "2") (pinfunction "ANODE_2") (pintype "passive"))
      (node (ref "J3") (pin "1") (pinfunction "1_1") (pintype "passive"))
      (node (ref "J3") (pin "2") (pinfunction "2_2") (pintype "passive"))
      (node (ref "J3") (pin "3") (pinfunction "3_3") (pintype "passive"))
      (node (ref "J3") (pin "4") (pinfunction "4_4") (pintype "passive"))
      (node (ref "U1") (pin "8") (pinfunction "8_8") (pintype "passive"))
    )
    (net (code "19") (name "P24V_MTR1") (class "Default")
      (node (ref "C10") (pin "1") (pinfunction "1_1") (pintype "passive"))
      (node (ref "C22") (pin "1") (pinfunction "1_1") (pintype "passive"))
      (node (ref "C7") (pin "1") (pinfunction "1_1") (pintype "passive"))
      (node (ref "C8") (pin "1") (pinfunction "1_1") (pintype "passive"))
      (node (ref "C9") (pin "1") (pinfunction "1_1") (pintype "passive"))
      (node (ref "D1") (pin "2") (pinfunction "ANODE_2") (pintype "passive"))
      (node (ref "J5") (pin "1") (pinfunction "1_1") (pintype "passive"))
      (node (ref "J5") (pin "2") (pinfunction "2_2") (pintype "passive"))
      (node (ref "J5") (pin "3") (pinfunction "3_3") (pintype "passive"))
      (node (ref "J5") (pin "4") (pinfunction "4_4") (pintype "passive"))
      (node (ref "R1") (pin "2") (pinfunction "2_2") (pintype "passive"))
      (node (ref "U2") (pin "8") (pinfunction "8_8") (pintype "passive"))
    )
    (net (code "20") (name "P24V_MTR2") (class "Default")
      (node (ref "C14") (pin "1") (pinfunction "1_1") (pintype "passive"))
      (node (ref "C15") (pin "1") (pinfunction "1_1") (pintype "passive"))
      (node (ref "C19") (pin "1") (pinfunction "1_1") (pintype "passive"))
      (node (ref "C20") (pin "1") (pinfunction "1_1") (pintype "passive"))
      (node (ref "C36") (pin "1") (pinfunction "1_1") (pintype "passive"))
      (node (ref "D7") (pin "2") (pinfunction "ANODE_2") (pintype "passive"))
      (node (ref "J7") (pin "1") (pinfunction "1_1") (pintype "passive"))
      (node (ref "J7") (pin "2") (pinfunction "2_2") (pintype "passive"))
      (node (ref "J7") (pin "3") (pinfunction "3_3") (pintype "passive"))
      (node (ref "J7") (pin "4") (pinfunction "4_4") (pintype "passive"))
      (node (ref "R10") (pin "2") (pinfunction "2_2") (pintype "passive"))
      (node (ref "U3") (pin "8") (pinfunction "8_8") (pintype "passive"))
    )
    (net (code "21") (name "P24V_MTR3") (class "Default")
      (node (ref "C23") (pin "1") (pinfunction "1_1") (pintype "passive"))
      (node (ref "C24") (pin "1") (pinfunction "1_1") (pintype "passive"))
      (node (ref "C25") (pin "1") (pinfunction "1_1") (pintype "passive"))
      (node (ref "C26") (pin "1") (pinfunction "1_1") (pintype "passive"))
      (node (ref "C33") (pin "1") (pinfunction "1_1") (pintype "passive"))
      (node (ref "D4") (pin "2") (pinfunction "ANODE_2") (pintype "passive"))
      (node (ref "J9") (pin "1") (pinfunction "1_1") (pintype "passive"))
      (node (ref "J9") (pin "2") (pinfunction "2_2") (pintype "passive"))
      (node (ref "J9") (pin "3") (pinfunction "3_3") (pintype "passive"))
      (node (ref "J9") (pin "4") (pinfunction "4_4") (pintype "passive"))
      (node (ref "R7") (pin "2") (pinfunction "2_2") (pintype "passive"))
      (node (ref "U4") (pin "8") (pinfunction "8_8") (pintype "passive"))
    )
    (net (code "22") (name "P48V") (class "Default")
      (node (ref "D3") (pin "2") (pinfunction "ANODE_2") (pintype "passive"))
      (node (ref "FL1") (pin "1") (pinfunction "+V_INPUT_1") (pintype "passive"))
      (node (ref "FL2") (pin "1") (pinfunction "+V_INPUT_1") (pintype "passive"))
      (node (ref "FL3") (pin "1") (pinfunction "+V_INPUT_1") (pintype "passive"))
      (node (ref "FL4") (pin "1") (pinfunction "+V_INPUT_1") (pintype "passive"))
      (node (ref "J1") (pin "1") (pinfunction "1_1") (pintype "passive"))
      (node (ref "J1") (pin "2") (pinfunction "2_2") (pintype "passive"))
      (node (ref "J1") (pin "3") (pinfunction "3_3") (pintype "passive"))
      (node (ref "J1") (pin "4") (pinfunction "4_4") (pintype "passive"))
    )
    (net (code "23") (name "RTN24_ISO") (class "Default")
      (node (ref "C1") (pin "2") (pinfunction "2_2") (pintype "passive"))
      (node (ref "C2") (pin "2") (pinfunction "2_2") (pintype "passive"))
      (node (ref "C3") (pin "2") (pinfunction "2_2") (pintype "passive"))
      (node (ref "C31") (pin "1") (pinfunction "1_1") (pintype "passive"))
      (node (ref "C4") (pin "2") (pinfunction "2_2") (pintype "passive"))
      (node (ref "C5") (pin "2") (pinfunction "2_2") (pintype "passive"))
      (node (ref "C6") (pin "2") (pinfunction "2_2") (pintype "passive"))
      (node (ref "J4") (pin "1") (pinfunction "1_1") (pintype "passive"))
      (node (ref "J4") (pin "2") (pinfunction "2_2") (pintype "passive"))
      (node (ref "J4") (pin "3") (pinfunction "3_3") (pintype "passive"))
      (node (ref "J4") (pin "4") (pinfunction "4_4") (pintype "passive"))
      (node (ref "R5") (pin "2") (pinfunction "2_2") (pintype "passive"))
      (node (ref "U1") (pin "4") (pinfunction "4_4") (pintype "passive"))
    )
    (net (code "24") (name "RTN48V") (class "Default")
      (node (ref "C10") (pin "2") (pinfunction "2_2") (pintype "passive"))
      (node (ref "C11") (pin "2") (pinfunction "2_2") (pintype "passive"))
      (node (ref "C12") (pin "2") (pinfunction "2_2") (pintype "passive"))
      (node (ref "C13") (pin "2") (pinfunction "2_2") (pintype "passive"))
      (node (ref "C14") (pin "2") (pinfunction "2_2") (pintype "passive"))
      (node (ref "C15") (pin "2") (pinfunction "2_2") (pintype "passive"))
      (node (ref "C16") (pin "2") (pinfunction "2_2") (pintype "passive"))
      (node (ref "C17") (pin "2") (pinfunction "2_2") (pintype "passive"))
      (node (ref "C18") (pin "2") (pinfunction "2_2") (pintype "passive"))
      (node (ref "C19") (pin "2") (pinfunction "2_2") (pintype "passive"))
      (node (ref "C20") (pin "2") (pinfunction "2_2") (pintype "passive"))
      (node (ref "C21") (pin "1") (pinfunction "1_1") (pintype "passive"))
      (node (ref "C23") (pin "2") (pinfunction "2_2") (pintype "passive"))
      (node (ref "C24") (pin "2") (pinfunction "2_2") (pintype "passive"))
      (node (ref "C25") (pin "2") (pinfunction "2_2") (pintype "passive"))
      (node (ref "C26") (pin "2") (pinfunction "2_2") (pintype "passive"))
      (node (ref "C27") (pin "2") (pinfunction "2_2") (pintype "passive"))
      (node (ref "C28") (pin "2") (pinfunction "2_2") (pintype "passive"))
      (node (ref "C29") (pin "2") (pinfunction "2_2") (pintype "passive"))
      (node (ref "C30") (pin "1") (pinfunction "1_1") (pintype "passive"))
      (node (ref "C35") (pin "1") (pinfunction "1_1") (pintype "passive"))
      (node (ref "C7") (pin "2") (pinfunction "2_2") (pintype "passive"))
      (node (ref "C8") (pin "2") (pinfunction "2_2") (pintype "passive"))
      (node (ref "C9") (pin "2") (pinfunction "2_2") (pintype "passive"))
      (node (ref "FL1") (pin "2") (pinfunction "-V_INPUT_2") (pintype "passive"))
      (node (ref "FL1") (pin "4") (pinfunction "-V_OUTPUT_4") (pintype "passive"))
      (node (ref "FL2") (pin "2") (pinfunction "-V_INPUT_2") (pintype "passive"))
      (node (ref "FL2") (pin "4") (pinfunction "-V_OUTPUT_4") (pintype "passive"))
      (node (ref "FL3") (pin "2") (pinfunction "-V_INPUT_2") (pintype "passive"))
      (node (ref "FL3") (pin "4") (pinfunction "-V_OUTPUT_4") (pintype "passive"))
      (node (ref "FL4") (pin "2") (pinfunction "-V_INPUT_2") (pintype "passive"))
      (node (ref "FL4") (pin "4") (pinfunction "-V_OUTPUT_4") (pintype "passive"))
      (node (ref "J10") (pin "1") (pinfunction "1_1") (pintype "passive"))
      (node (ref "J10") (pin "2") (pinfunction "2_2") (pintype "passive"))
      (node (ref "J10") (pin "3") (pinfunction "3_3") (pintype "passive"))
      (node (ref "J10") (pin "4") (pinfunction "4_4") (pintype "passive"))
      (node (ref "J2") (pin "1") (pinfunction "1_1") (pintype "passive"))
      (node (ref "J2") (pin "2") (pinfunction "2_2") (pintype "passive"))
      (node (ref "J2") (pin "3") (pinfunction "3_3") (pintype "passive"))
      (node (ref "J2") (pin "4") (pinfunction "4_4") (pintype "passive"))
      (node (ref "J6") (pin "1") (pinfunction "1_1") (pintype "passive"))
      (node (ref "J6") (pin "2") (pinfunction "2_2") (pintype "passive"))
      (node (ref "J6") (pin "3") (pinfunction "3_3") (pintype "passive"))
      (node (ref "J6") (pin "4") (pinfunction "4_4") (pintype "passive"))
      (node (ref "J8") (pin "1") (pinfunction "1_1") (pintype "passive"))
      (node (ref "J8") (pin "2") (pinfunction "2_2") (pintype "passive"))
      (node (ref "J8") (pin "3") (pinfunction "3_3") (pintype "passive"))
      (node (ref "J8") (pin "4") (pinfunction "4_4") (pintype "passive"))
      (node (ref "R11") (pin "1") (pinfunction "1_1") (pintype "passive"))
      (node (ref "R12") (pin "2") (pinfunction "2_2") (pintype "passive"))
      (node (ref "R13") (pin "2") (pinfunction "2_2") (pintype "passive"))
      (node (ref "R2") (pin "1") (pinfunction "1_1") (pintype "passive"))
      (node (ref "R4") (pin "1") (pinfunction "1_1") (pintype "passive"))
      (node (ref "R6") (pin "2") (pinfunction "2_2") (pintype "passive"))
      (node (ref "R8") (pin "2") (pinfunction "2_2") (pintype "passive"))
      (node (ref "R9") (pin "1") (pinfunction "1_1") (pintype "passive"))
      (node (ref "U1") (pin "3") (pinfunction "3_3") (pintype "passive"))
      (node (ref "U2") (pin "2") (pinfunction "2_2") (pintype "passive"))
      (node (ref "U2") (pin "3") (pinfunction "3_3") (pintype "passive"))
      (node (ref "U2") (pin "4") (pinfunction "4_4") (pintype "passive"))
      (node (ref "U3") (pin "2") (pinfunction "2_2") (pintype "passive"))
      (node (ref "U3") (pin "3") (pinfunction "3_3") (pintype "passive"))
      (node (ref "U3") (pin "4") (pinfunction "4_4") (pintype "passive"))
      (node (ref "U4") (pin "2") (pinfunction "2_2") (pintype "passive"))
      (node (ref "U4") (pin "3") (pinfunction "3_3") (pintype "passive"))
      (node (ref "U4") (pin "4") (pinfunction "4_4") (pintype "passive"))
    )
    (net (code "25") (name "unconnected-(U1-Pad5)") (class "Default")
      (node (ref "U1") (pin "5") (pinfunction "5_5") (pintype "passive+no_connect"))
    )
    (net (code "26") (name "unconnected-(U1-Pad6)") (class "Default")
      (node (ref "U1") (pin "6") (pinfunction "6_6") (pintype "passive+no_connect"))
    )
    (net (code "27") (name "unconnected-(U1-Pad7)") (class "Default")
      (node (ref "U1") (pin "7") (pinfunction "7_7") (pintype "passive+no_connect"))
    )
    (net (code "28") (name "unconnected-(U2-Pad5)") (class "Default")
      (node (ref "U2") (pin "5") (pinfunction "5_5") (pintype "passive+no_connect"))
    )
    (net (code "29") (name "unconnected-(U3-Pad5)") (class "Default")
      (node (ref "U3") (pin "5") (pinfunction "5_5") (pintype "passive+no_connect"))
    )
    (net (code "30") (name "unconnected-(U4-Pad5)") (class "Default")
      (node (ref "U4") (pin "5") (pinfunction "5_5") (pintype "passive+no_connect"))
    )
  )
)
